# USB.net
KiCad netlist of a schematic drawn in Altium Designer
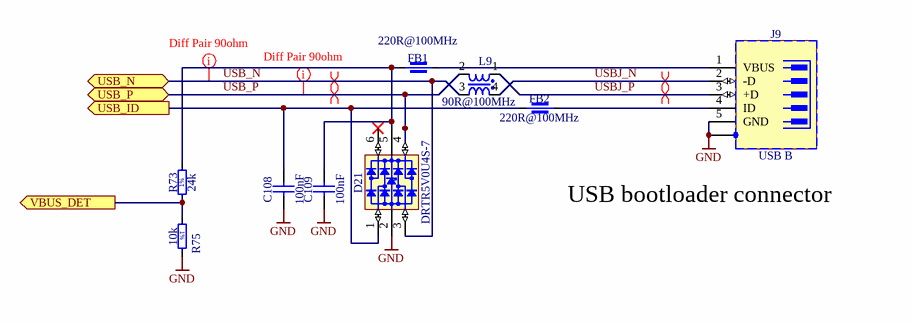
[diagram p0: USB.SchDoc]

(export (version "E")
  (design (tool "Eeschema 10.0.6"))
  (components
    (comp (ref "C108")
      (value "100nF")
      (footprint "CAPC1005X55N")
      (description "Non-polarised capacitor")
      (fields
        (field (name "PART NUMBER") "CC0402_100NF_16V_10%_X5R")
        (field (name "VOLTAGE") "16V")
        (field (name "AUTHOR") "CERN DEM JLC")
      )
      (libsource (lib "Capacitors") (part "Capacitor - non polarized"))
    )
    (comp (ref "C109")
      (value "100nF")
      (footprint "CAPC1005X55N")
      (description "Non-polarised capacitor")
      (fields
        (field (name "PART NUMBER") "CC0402_100NF_16V_10%_X5R")
        (field (name "VOLTAGE") "16V")
        (field (name "AUTHOR") "CERN DEM JLC")
      )
      (libsource (lib "Capacitors") (part "Capacitor - non polarized"))
    )
    (comp (ref "D21")
      (value "DRTR5V0U4S-7")
      (footprint "SOT65P210X110-6N")
      (description "Integrated Quad Ultra-Low Capacitance ESD Protection")
      (fields (field (name "MANUFACTURER") "DIODES") (field (name "AUTHOR") "GK"))
      (libsource (lib "Diodes") (part "D_TVS_DRTR5V0U4S-7"))
    )
    (comp (ref "FB1")
      (value "220R@100MHz")
      (footprint "INDC1005X55N")
      (fields
        (field (name "PART NUMBER") "IND0402_MURATA_BLM15HB221SN1")
        (field (name "POWER") "250mA")
        (field (name "TOLERANCE") "±25%")
        (field (name "AUTHOR") "CERN DEM JLC")
      )
      (libsource (lib "Inductors & Transformers") (part "Ferrite Bead"))
    )
    (comp (ref "FB2")
      (value "220R@100MHz")
      (footprint "INDC1005X55N")
      (fields
        (field (name "PART NUMBER") "IND0402_MURATA_BLM15HB221SN1")
        (field (name "POWER") "250mA")
        (field (name "TOLERANCE") "±25%")
        (field (name "AUTHOR") "CERN DEM JLC")
      )
      (libsource (lib "Inductors & Transformers") (part "Ferrite Bead"))
    )
    (comp (ref "J9")
      (value "USB B")
      (footprint "MOLEX_47642-1001")
      (description "5 Pin + 1 Shield USB Receptacle")
      (fields
        (field (name "PART NUMBER") "MOLEX_47642-1001")
        (field (name "MANUFACTURER") "MOLEX")
        (field (name "AUTHOR") "CERN DEM BC")
      )
      (libsource (lib "Connectors") (part "Connector USB 5 Pin + 1Shield"))
    )
    (comp (ref "L9")
      (value "90R@100MHz")
      (footprint "IND_MURATA_DLW21S")
      (description "Inductor Common Mode")
      (fields
        (field (name "PART NUMBER") "IND_MURATA_DLW21SN900SQ2L")
        (field (name "POWER") "330mA")
        (field (name "AUTHOR") "CERN DEM JLC")
      )
      (libsource (lib "Inductors & Transformers") (part "Inductor Common Mode 1Dot-2 4Dot-3"))
    )
    (comp (ref "R73")
      (value "24k")
      (footprint "RESC1608X55N")
      (description "Resistor - 1%")
      (fields
        (field (name "PART NUMBER") "R0603_24K_1%_0.1W_100PPM")
        (field (name "POWER") "0.1W")
        (field (name "AUTHOR") "CERN DEM JLC")
      )
      (libsource (lib "Resistors") (part "Resistor - 1%"))
    )
    (comp (ref "R75")
      (value "10k")
      (footprint "RESC1005X40N")
      (description "Resistor - 1%")
      (fields
        (field (name "PART NUMBER") "R0402_10K_1%_0.0625W_100PPM")
        (field (name "POWER") "0.0625W")
        (field (name "AUTHOR") "CERN DEM JLC")
      )
      (libsource (lib "Resistors") (part "Resistor - 1%"))
    )
  )
  (nets
    (net (code "1") (name "/USBJ_N") (class "Default")
      (node (ref "J9") (pin "2") (pinfunction "-D_2") (pintype "bidirectional"))
      (node (ref "L9") (pin "4") (pinfunction "4_4") (pintype "passive"))
    )
    (net (code "2") (name "/USBJ_P") (class "Default")
      (node (ref "J9") (pin "3") (pinfunction "+D_3") (pintype "bidirectional"))
      (node (ref "L9") (pin "1") (pinfunction "1_1") (pintype "passive"))
    )
    (net (code "3") (name "/USB_ID") (class "Default")
      (node (ref "C108") (pin "2") (pinfunction "2_2") (pintype "passive"))
      (node (ref "D21") (pin "1") (pinfunction "I/O1_1") (pintype "bidirectional"))
      (node (ref "FB2") (pin "1") (pinfunction "1_1") (pintype "passive"))
    )
    (net (code "4") (name "/USB_N") (class "Default")
      (node (ref "D21") (pin "3") (pinfunction "I/O2_3") (pintype "bidirectional"))
      (node (ref "L9") (pin "3") (pinfunction "3_3") (pintype "passive"))
    )
    (net (code "5") (name "/USB_P") (class "Default")
      (node (ref "D21") (pin "4") (pinfunction "I/O3_4") (pintype "bidirectional"))
      (node (ref "L9") (pin "2") (pinfunction "2_2") (pintype "passive"))
    )
    (net (code "6") (name "/VBUS_DET") (class "Default")
      (node (ref "R73") (pin "1") (pinfunction "1_1") (pintype "passive"))
      (node (ref "R75") (pin "1") (pinfunction "1_1") (pintype "passive"))
    )
    (net (code "7") (name "GND") (class "Default")
      (node (ref "C108") (pin "1") (pinfunction "1_1") (pintype "passive"))
      (node (ref "C109") (pin "1") (pinfunction "1_1") (pintype "passive"))
      (node (ref "D21") (pin "2") (pinfunction "GND_2") (pintype "power_in"))
      (node (ref "J9") (pin "5") (pinfunction "GND_5") (pintype "power_in"))
      (node (ref "J9") (pin "6") (pinfunction "SH_6") (pintype "power_in"))
      (node (ref "R75") (pin "2") (pinfunction "2_2") (pintype "passive"))
    )
    (net (code "8") (name "Net-(D21-VBUS)") (class "Default")
      (node (ref "C109") (pin "2") (pinfunction "2_2") (pintype "passive"))
      (node (ref "D21") (pin "5") (pinfunction "VBUS_5") (pintype "power_in"))
      (node (ref "FB1") (pin "1") (pinfunction "1_1") (pintype "passive"))
      (node (ref "R73") (pin "2") (pinfunction "2_2") (pintype "passive"))
    )
    (net (code "9") (name "Net-(J9-ID)") (class "Default")
      (node (ref "FB2") (pin "2") (pinfunction "2_2") (pintype "passive"))
      (node (ref "J9") (pin "4") (pinfunction "ID_4") (pintype "passive"))
    )
    (net (code "10") (name "Net-(J9-VBUS)") (class "Default")
      (node (ref "FB1") (pin "2") (pinfunction "2_2") (pintype "passive"))
      (node (ref "J9") (pin "1") (pinfunction "VBUS_1") (pintype "power_in"))
    )
    (net (code "11") (name "unconnected-(D21-I{slash}O4-Pad6)") (class "Default")
      (node (ref "D21") (pin "6") (pinfunction "I/O4_6") (pintype "bidirectional+no_connect"))
    )
  )
)
